# r2r-dac.net
KiCad netlist of a schematic drawn in EAGLE
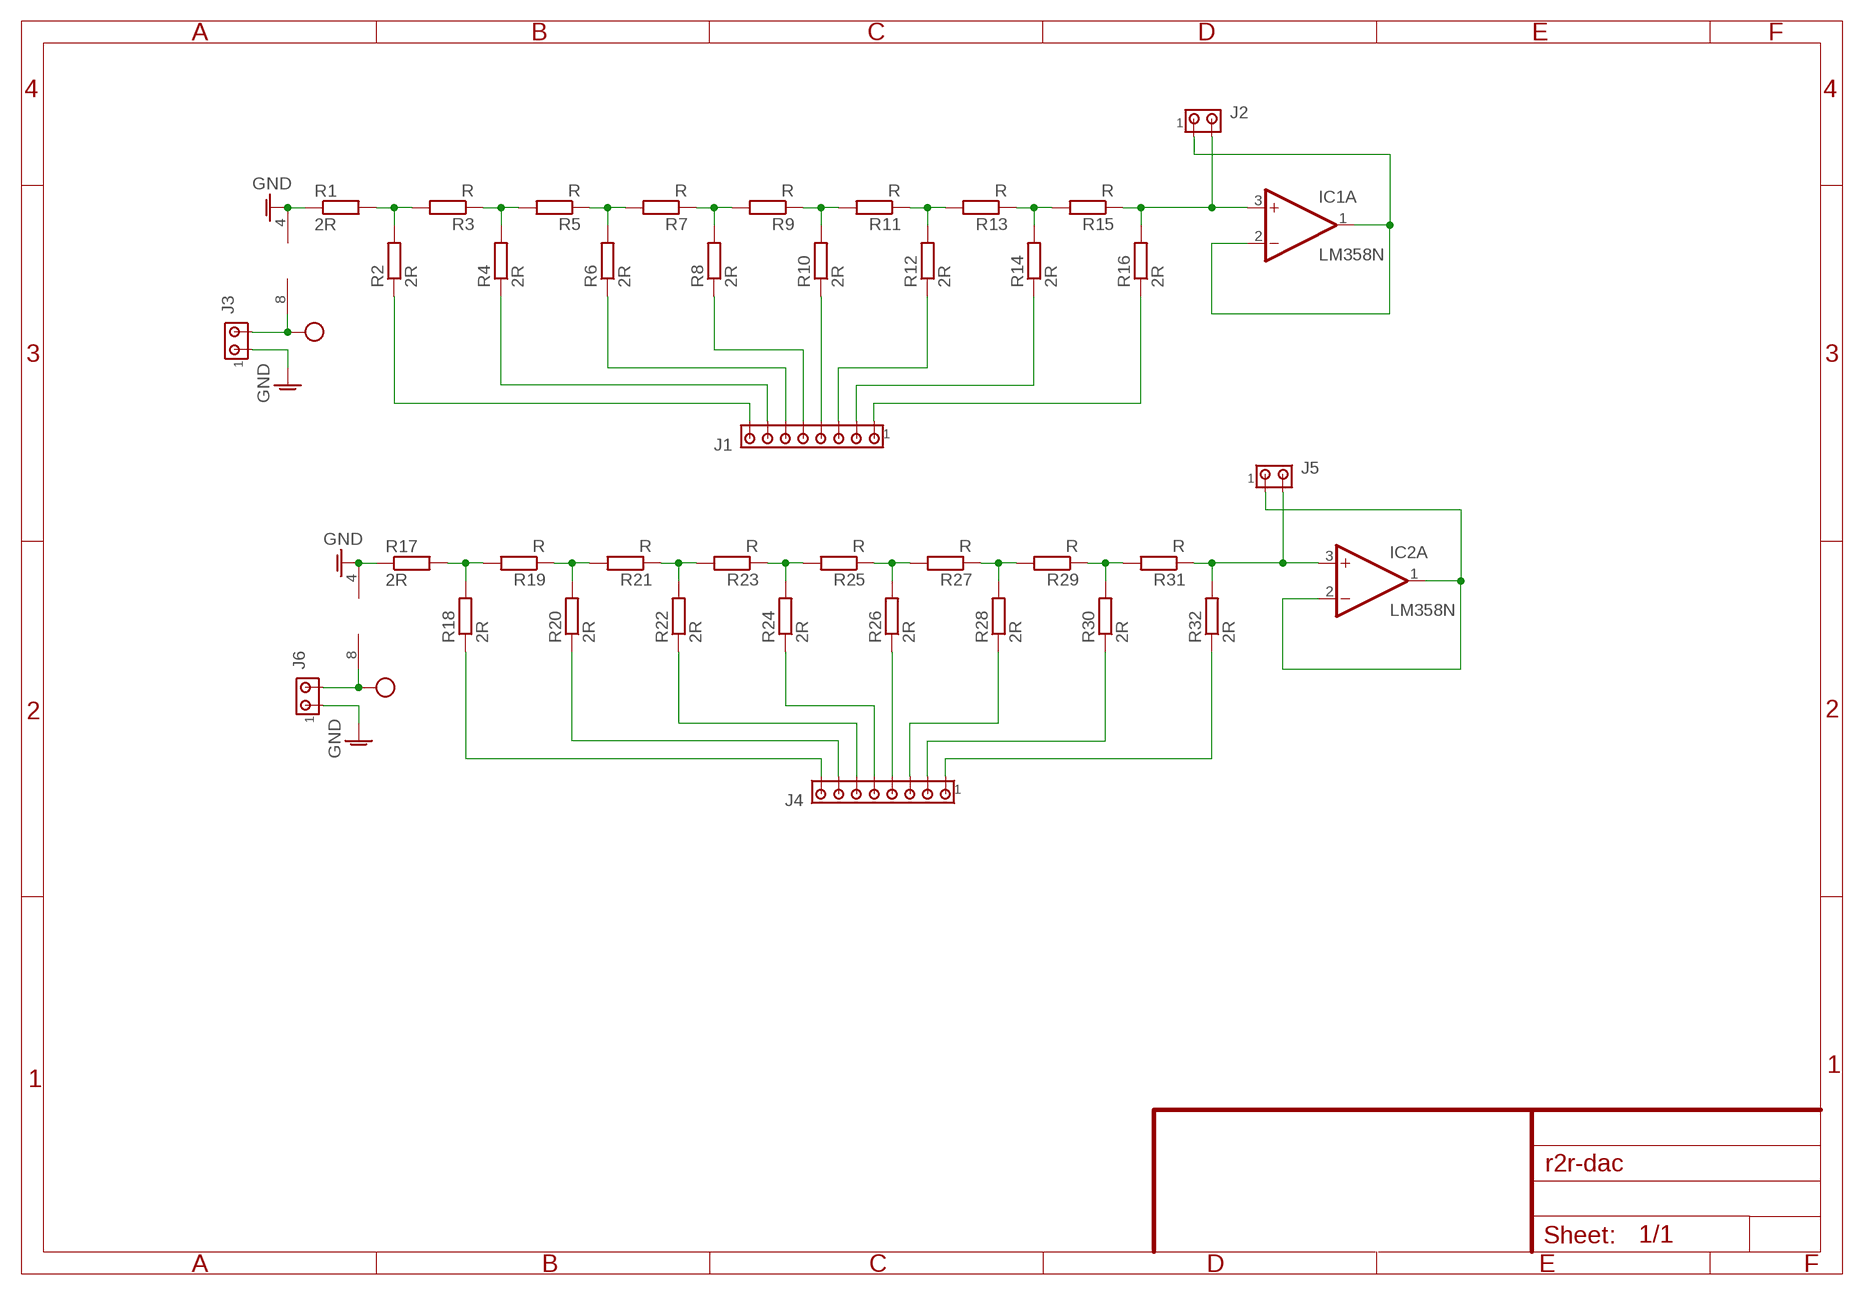
[diagram p0: schematic, sheet 1]

(export (version "E")
  (design (tool "Eeschema 10.0.6"))
  (components
    (comp (ref "IC1")
      (value "LM358N")
      (footprint "eagle-import:DIL08")
      (libsource (lib "eagle-import") (part "LM358N"))
    )
    (comp (ref "IC2")
      (value "LM358N")
      (footprint "eagle-import:DIL08")
      (libsource (lib "eagle-import") (part "LM358N"))
    )
    (comp (ref "J1")
      (value "MTA08-100")
      (footprint "eagle-import:10X08MTA")
      (libsource (lib "eagle-import") (part "MTA08-100"))
    )
    (comp (ref "J2")
      (value "MTA02-100")
      (footprint "eagle-import:10X02MTA")
      (libsource (lib "eagle-import") (part "MTA02-100"))
    )
    (comp (ref "J3")
      (value "MTA02-100")
      (footprint "eagle-import:10X02MTA")
      (libsource (lib "eagle-import") (part "MTA02-100"))
    )
    (comp (ref "J4")
      (value "MTA08-100")
      (footprint "eagle-import:10X08MTA")
      (libsource (lib "eagle-import") (part "MTA08-100"))
    )
    (comp (ref "J5")
      (value "MTA02-100")
      (footprint "eagle-import:10X02MTA")
      (libsource (lib "eagle-import") (part "MTA02-100"))
    )
    (comp (ref "J6")
      (value "MTA02-100")
      (footprint "eagle-import:10X02MTA")
      (libsource (lib "eagle-import") (part "MTA02-100"))
    )
    (comp (ref "R1")
      (value "2R")
      (footprint "eagle-import:0207_10")
      (libsource (lib "eagle-import") (part "R-EU_0207/10"))
    )
    (comp (ref "R2")
      (value "2R")
      (footprint "eagle-import:0207_10")
      (libsource (lib "eagle-import") (part "R-EU_0207/10"))
    )
    (comp (ref "R3")
      (value "R")
      (footprint "eagle-import:0207_10")
      (libsource (lib "eagle-import") (part "R-EU_0207/10"))
    )
    (comp (ref "R4")
      (value "2R")
      (footprint "eagle-import:0207_10")
      (libsource (lib "eagle-import") (part "R-EU_0207/10"))
    )
    (comp (ref "R5")
      (value "R")
      (footprint "eagle-import:0207_10")
      (libsource (lib "eagle-import") (part "R-EU_0207/10"))
    )
    (comp (ref "R6")
      (value "2R")
      (footprint "eagle-import:0207_10")
      (libsource (lib "eagle-import") (part "R-EU_0207/10"))
    )
    (comp (ref "R7")
      (value "R")
      (footprint "eagle-import:0207_10")
      (libsource (lib "eagle-import") (part "R-EU_0207/10"))
    )
    (comp (ref "R8")
      (value "2R")
      (footprint "eagle-import:0207_10")
      (libsource (lib "eagle-import") (part "R-EU_0207/10"))
    )
    (comp (ref "R9")
      (value "R")
      (footprint "eagle-import:0207_10")
      (libsource (lib "eagle-import") (part "R-EU_0207/10"))
    )
    (comp (ref "R10")
      (value "2R")
      (footprint "eagle-import:0207_10")
      (libsource (lib "eagle-import") (part "R-EU_0207/10"))
    )
    (comp (ref "R11")
      (value "R")
      (footprint "eagle-import:0207_10")
      (libsource (lib "eagle-import") (part "R-EU_0207/10"))
    )
    (comp (ref "R12")
      (value "2R")
      (footprint "eagle-import:0207_10")
      (libsource (lib "eagle-import") (part "R-EU_0207/10"))
    )
    (comp (ref "R13")
      (value "R")
      (footprint "eagle-import:0207_10")
      (libsource (lib "eagle-import") (part "R-EU_0207/10"))
    )
    (comp (ref "R14")
      (value "2R")
      (footprint "eagle-import:0207_10")
      (libsource (lib "eagle-import") (part "R-EU_0207/10"))
    )
    (comp (ref "R15")
      (value "R")
      (footprint "eagle-import:0207_10")
      (libsource (lib "eagle-import") (part "R-EU_0207/10"))
    )
    (comp (ref "R16")
      (value "2R")
      (footprint "eagle-import:0207_10")
      (libsource (lib "eagle-import") (part "R-EU_0207/10"))
    )
    (comp (ref "R17")
      (value "2R")
      (footprint "eagle-import:0207_10")
      (libsource (lib "eagle-import") (part "R-EU_0207/10"))
    )
    (comp (ref "R18")
      (value "2R")
      (footprint "eagle-import:0207_10")
      (libsource (lib "eagle-import") (part "R-EU_0207/10"))
    )
    (comp (ref "R19")
      (value "R")
      (footprint "eagle-import:0207_10")
      (libsource (lib "eagle-import") (part "R-EU_0207/10"))
    )
    (comp (ref "R20")
      (value "2R")
      (footprint "eagle-import:0207_10")
      (libsource (lib "eagle-import") (part "R-EU_0207/10"))
    )
    (comp (ref "R21")
      (value "R")
      (footprint "eagle-import:0207_10")
      (libsource (lib "eagle-import") (part "R-EU_0207/10"))
    )
    (comp (ref "R22")
      (value "2R")
      (footprint "eagle-import:0207_10")
      (libsource (lib "eagle-import") (part "R-EU_0207/10"))
    )
    (comp (ref "R23")
      (value "R")
      (footprint "eagle-import:0207_10")
      (libsource (lib "eagle-import") (part "R-EU_0207/10"))
    )
    (comp (ref "R24")
      (value "2R")
      (footprint "eagle-import:0207_10")
      (libsource (lib "eagle-import") (part "R-EU_0207/10"))
    )
    (comp (ref "R25")
      (value "R")
      (footprint "eagle-import:0207_10")
      (libsource (lib "eagle-import") (part "R-EU_0207/10"))
    )
    (comp (ref "R26")
      (value "2R")
      (footprint "eagle-import:0207_10")
      (libsource (lib "eagle-import") (part "R-EU_0207/10"))
    )
    (comp (ref "R27")
      (value "R")
      (footprint "eagle-import:0207_10")
      (libsource (lib "eagle-import") (part "R-EU_0207/10"))
    )
    (comp (ref "R28")
      (value "2R")
      (footprint "eagle-import:0207_10")
      (libsource (lib "eagle-import") (part "R-EU_0207/10"))
    )
    (comp (ref "R29")
      (value "R")
      (footprint "eagle-import:0207_10")
      (libsource (lib "eagle-import") (part "R-EU_0207/10"))
    )
    (comp (ref "R30")
      (value "2R")
      (footprint "eagle-import:0207_10")
      (libsource (lib "eagle-import") (part "R-EU_0207/10"))
    )
    (comp (ref "R31")
      (value "R")
      (footprint "eagle-import:0207_10")
      (libsource (lib "eagle-import") (part "R-EU_0207/10"))
    )
    (comp (ref "R32")
      (value "2R")
      (footprint "eagle-import:0207_10")
      (libsource (lib "eagle-import") (part "R-EU_0207/10"))
    )
  )
  (nets
    (net (code "1") (name "GND") (class "Default")
      (node (ref "IC1") (pin "4") (pinfunction "V-_4") (pintype "power_in"))
      (node (ref "IC2") (pin "4") (pinfunction "V-_4") (pintype "power_in"))
      (node (ref "J3") (pin "1") (pinfunction "1_1") (pintype "passive"))
      (node (ref "J6") (pin "1") (pinfunction "1_1") (pintype "passive"))
      (node (ref "R1") (pin "1") (pinfunction "1_1") (pintype "passive"))
      (node (ref "R17") (pin "1") (pinfunction "1_1") (pintype "passive"))
    )
    (net (code "2") (name "Net-(IC1A-+IN)") (class "Default")
      (node (ref "IC1") (pin "3") (pinfunction "+IN_3") (pintype "input"))
      (node (ref "J2") (pin "2") (pinfunction "2_2") (pintype "passive"))
      (node (ref "R15") (pin "1") (pinfunction "1_1") (pintype "passive"))
      (node (ref "R16") (pin "2") (pinfunction "2_2") (pintype "passive"))
    )
    (net (code "3") (name "Net-(IC1A--IN)") (class "Default")
      (node (ref "IC1") (pin "1") (pinfunction "OUT_1") (pintype "output"))
      (node (ref "IC1") (pin "2") (pinfunction "-IN_2") (pintype "input"))
      (node (ref "J2") (pin "1") (pinfunction "1_1") (pintype "passive"))
    )
    (net (code "4") (name "Net-(IC2A-+IN)") (class "Default")
      (node (ref "IC2") (pin "3") (pinfunction "+IN_3") (pintype "input"))
      (node (ref "J5") (pin "2") (pinfunction "2_2") (pintype "passive"))
      (node (ref "R31") (pin "1") (pinfunction "1_1") (pintype "passive"))
      (node (ref "R32") (pin "2") (pinfunction "2_2") (pintype "passive"))
    )
    (net (code "5") (name "Net-(IC2A--IN)") (class "Default")
      (node (ref "IC2") (pin "1") (pinfunction "OUT_1") (pintype "output"))
      (node (ref "IC2") (pin "2") (pinfunction "-IN_2") (pintype "input"))
      (node (ref "J5") (pin "1") (pinfunction "1_1") (pintype "passive"))
    )
    (net (code "6") (name "Net-(J1-Pad1)") (class "Default")
      (node (ref "J1") (pin "1") (pinfunction "1_1") (pintype "passive"))
      (node (ref "R16") (pin "1") (pinfunction "1_1") (pintype "passive"))
    )
    (net (code "7") (name "Net-(J1-Pad2)") (class "Default")
      (node (ref "J1") (pin "2") (pinfunction "2_2") (pintype "passive"))
      (node (ref "R14") (pin "1") (pinfunction "1_1") (pintype "passive"))
    )
    (net (code "8") (name "Net-(J1-Pad3)") (class "Default")
      (node (ref "J1") (pin "3") (pinfunction "3_3") (pintype "passive"))
      (node (ref "R12") (pin "1") (pinfunction "1_1") (pintype "passive"))
    )
    (net (code "9") (name "Net-(J1-Pad4)") (class "Default")
      (node (ref "J1") (pin "4") (pinfunction "4_4") (pintype "passive"))
      (node (ref "R10") (pin "1") (pinfunction "1_1") (pintype "passive"))
    )
    (net (code "10") (name "Net-(J1-Pad5)") (class "Default")
      (node (ref "J1") (pin "5") (pinfunction "5_5") (pintype "passive"))
      (node (ref "R8") (pin "1") (pinfunction "1_1") (pintype "passive"))
    )
    (net (code "11") (name "Net-(J1-Pad6)") (class "Default")
      (node (ref "J1") (pin "6") (pinfunction "6_6") (pintype "passive"))
      (node (ref "R6") (pin "1") (pinfunction "1_1") (pintype "passive"))
    )
    (net (code "12") (name "Net-(J1-Pad7)") (class "Default")
      (node (ref "J1") (pin "7") (pinfunction "7_7") (pintype "passive"))
      (node (ref "R4") (pin "1") (pinfunction "1_1") (pintype "passive"))
    )
    (net (code "13") (name "Net-(J1-Pad8)") (class "Default")
      (node (ref "J1") (pin "8") (pinfunction "8_8") (pintype "passive"))
      (node (ref "R2") (pin "1") (pinfunction "1_1") (pintype "passive"))
    )
    (net (code "14") (name "Net-(J4-Pad1)") (class "Default")
      (node (ref "J4") (pin "1") (pinfunction "1_1") (pintype "passive"))
      (node (ref "R32") (pin "1") (pinfunction "1_1") (pintype "passive"))
    )
    (net (code "15") (name "Net-(J4-Pad2)") (class "Default")
      (node (ref "J4") (pin "2") (pinfunction "2_2") (pintype "passive"))
      (node (ref "R30") (pin "1") (pinfunction "1_1") (pintype "passive"))
    )
    (net (code "16") (name "Net-(J4-Pad3)") (class "Default")
      (node (ref "J4") (pin "3") (pinfunction "3_3") (pintype "passive"))
      (node (ref "R28") (pin "1") (pinfunction "1_1") (pintype "passive"))
    )
    (net (code "17") (name "Net-(J4-Pad4)") (class "Default")
      (node (ref "J4") (pin "4") (pinfunction "4_4") (pintype "passive"))
      (node (ref "R26") (pin "1") (pinfunction "1_1") (pintype "passive"))
    )
    (net (code "18") (name "Net-(J4-Pad5)") (class "Default")
      (node (ref "J4") (pin "5") (pinfunction "5_5") (pintype "passive"))
      (node (ref "R24") (pin "1") (pinfunction "1_1") (pintype "passive"))
    )
    (net (code "19") (name "Net-(J4-Pad6)") (class "Default")
      (node (ref "J4") (pin "6") (pinfunction "6_6") (pintype "passive"))
      (node (ref "R22") (pin "1") (pinfunction "1_1") (pintype "passive"))
    )
    (net (code "20") (name "Net-(J4-Pad7)") (class "Default")
      (node (ref "J4") (pin "7") (pinfunction "7_7") (pintype "passive"))
      (node (ref "R20") (pin "1") (pinfunction "1_1") (pintype "passive"))
    )
    (net (code "21") (name "Net-(J4-Pad8)") (class "Default")
      (node (ref "J4") (pin "8") (pinfunction "8_8") (pintype "passive"))
      (node (ref "R18") (pin "1") (pinfunction "1_1") (pintype "passive"))
    )
    (net (code "22") (name "Net-(R1-Pad2)") (class "Default")
      (node (ref "R1") (pin "2") (pinfunction "2_2") (pintype "passive"))
      (node (ref "R2") (pin "2") (pinfunction "2_2") (pintype "passive"))
      (node (ref "R3") (pin "2") (pinfunction "2_2") (pintype "passive"))
    )
    (net (code "23") (name "Net-(R3-Pad1)") (class "Default")
      (node (ref "R3") (pin "1") (pinfunction "1_1") (pintype "passive"))
      (node (ref "R4") (pin "2") (pinfunction "2_2") (pintype "passive"))
      (node (ref "R5") (pin "2") (pinfunction "2_2") (pintype "passive"))
    )
    (net (code "24") (name "Net-(R5-Pad1)") (class "Default")
      (node (ref "R5") (pin "1") (pinfunction "1_1") (pintype "passive"))
      (node (ref "R6") (pin "2") (pinfunction "2_2") (pintype "passive"))
      (node (ref "R7") (pin "2") (pinfunction "2_2") (pintype "passive"))
    )
    (net (code "25") (name "Net-(R7-Pad1)") (class "Default")
      (node (ref "R7") (pin "1") (pinfunction "1_1") (pintype "passive"))
      (node (ref "R8") (pin "2") (pinfunction "2_2") (pintype "passive"))
      (node (ref "R9") (pin "2") (pinfunction "2_2") (pintype "passive"))
    )
    (net (code "26") (name "Net-(R10-Pad2)") (class "Default")
      (node (ref "R10") (pin "2") (pinfunction "2_2") (pintype "passive"))
      (node (ref "R11") (pin "2") (pinfunction "2_2") (pintype "passive"))
      (node (ref "R9") (pin "1") (pinfunction "1_1") (pintype "passive"))
    )
    (net (code "27") (name "Net-(R11-Pad1)") (class "Default")
      (node (ref "R11") (pin "1") (pinfunction "1_1") (pintype "passive"))
      (node (ref "R12") (pin "2") (pinfunction "2_2") (pintype "passive"))
      (node (ref "R13") (pin "2") (pinfunction "2_2") (pintype "passive"))
    )
    (net (code "28") (name "Net-(R13-Pad1)") (class "Default")
      (node (ref "R13") (pin "1") (pinfunction "1_1") (pintype "passive"))
      (node (ref "R14") (pin "2") (pinfunction "2_2") (pintype "passive"))
      (node (ref "R15") (pin "2") (pinfunction "2_2") (pintype "passive"))
    )
    (net (code "29") (name "Net-(R17-Pad2)") (class "Default")
      (node (ref "R17") (pin "2") (pinfunction "2_2") (pintype "passive"))
      (node (ref "R18") (pin "2") (pinfunction "2_2") (pintype "passive"))
      (node (ref "R19") (pin "2") (pinfunction "2_2") (pintype "passive"))
    )
    (net (code "30") (name "Net-(R19-Pad1)") (class "Default")
      (node (ref "R19") (pin "1") (pinfunction "1_1") (pintype "passive"))
      (node (ref "R20") (pin "2") (pinfunction "2_2") (pintype "passive"))
      (node (ref "R21") (pin "2") (pinfunction "2_2") (pintype "passive"))
    )
    (net (code "31") (name "Net-(R21-Pad1)") (class "Default")
      (node (ref "R21") (pin "1") (pinfunction "1_1") (pintype "passive"))
      (node (ref "R22") (pin "2") (pinfunction "2_2") (pintype "passive"))
      (node (ref "R23") (pin "2") (pinfunction "2_2") (pintype "passive"))
    )
    (net (code "32") (name "Net-(R23-Pad1)") (class "Default")
      (node (ref "R23") (pin "1") (pinfunction "1_1") (pintype "passive"))
      (node (ref "R24") (pin "2") (pinfunction "2_2") (pintype "passive"))
      (node (ref "R25") (pin "2") (pinfunction "2_2") (pintype "passive"))
    )
    (net (code "33") (name "Net-(R25-Pad1)") (class "Default")
      (node (ref "R25") (pin "1") (pinfunction "1_1") (pintype "passive"))
      (node (ref "R26") (pin "2") (pinfunction "2_2") (pintype "passive"))
      (node (ref "R27") (pin "2") (pinfunction "2_2") (pintype "passive"))
    )
    (net (code "34") (name "Net-(R27-Pad1)") (class "Default")
      (node (ref "R27") (pin "1") (pinfunction "1_1") (pintype "passive"))
      (node (ref "R28") (pin "2") (pinfunction "2_2") (pintype "passive"))
      (node (ref "R29") (pin "2") (pinfunction "2_2") (pintype "passive"))
    )
    (net (code "35") (name "Net-(R29-Pad1)") (class "Default")
      (node (ref "R29") (pin "1") (pinfunction "1_1") (pintype "passive"))
      (node (ref "R30") (pin "2") (pinfunction "2_2") (pintype "passive"))
      (node (ref "R31") (pin "2") (pinfunction "2_2") (pintype "passive"))
    )
    (net (code "36") (name "VDD") (class "Default")
      (node (ref "IC1") (pin "8") (pinfunction "V+_8") (pintype "power_in"))
      (node (ref "IC2") (pin "8") (pinfunction "V+_8") (pintype "power_in"))
      (node (ref "J3") (pin "2") (pinfunction "2_2") (pintype "passive"))
      (node (ref "J6") (pin "2") (pinfunction "2_2") (pintype "passive"))
    )
  )
)
